# MCU089A_F280025C_Device.net
KiCad netlist of a schematic drawn in Altium Designer
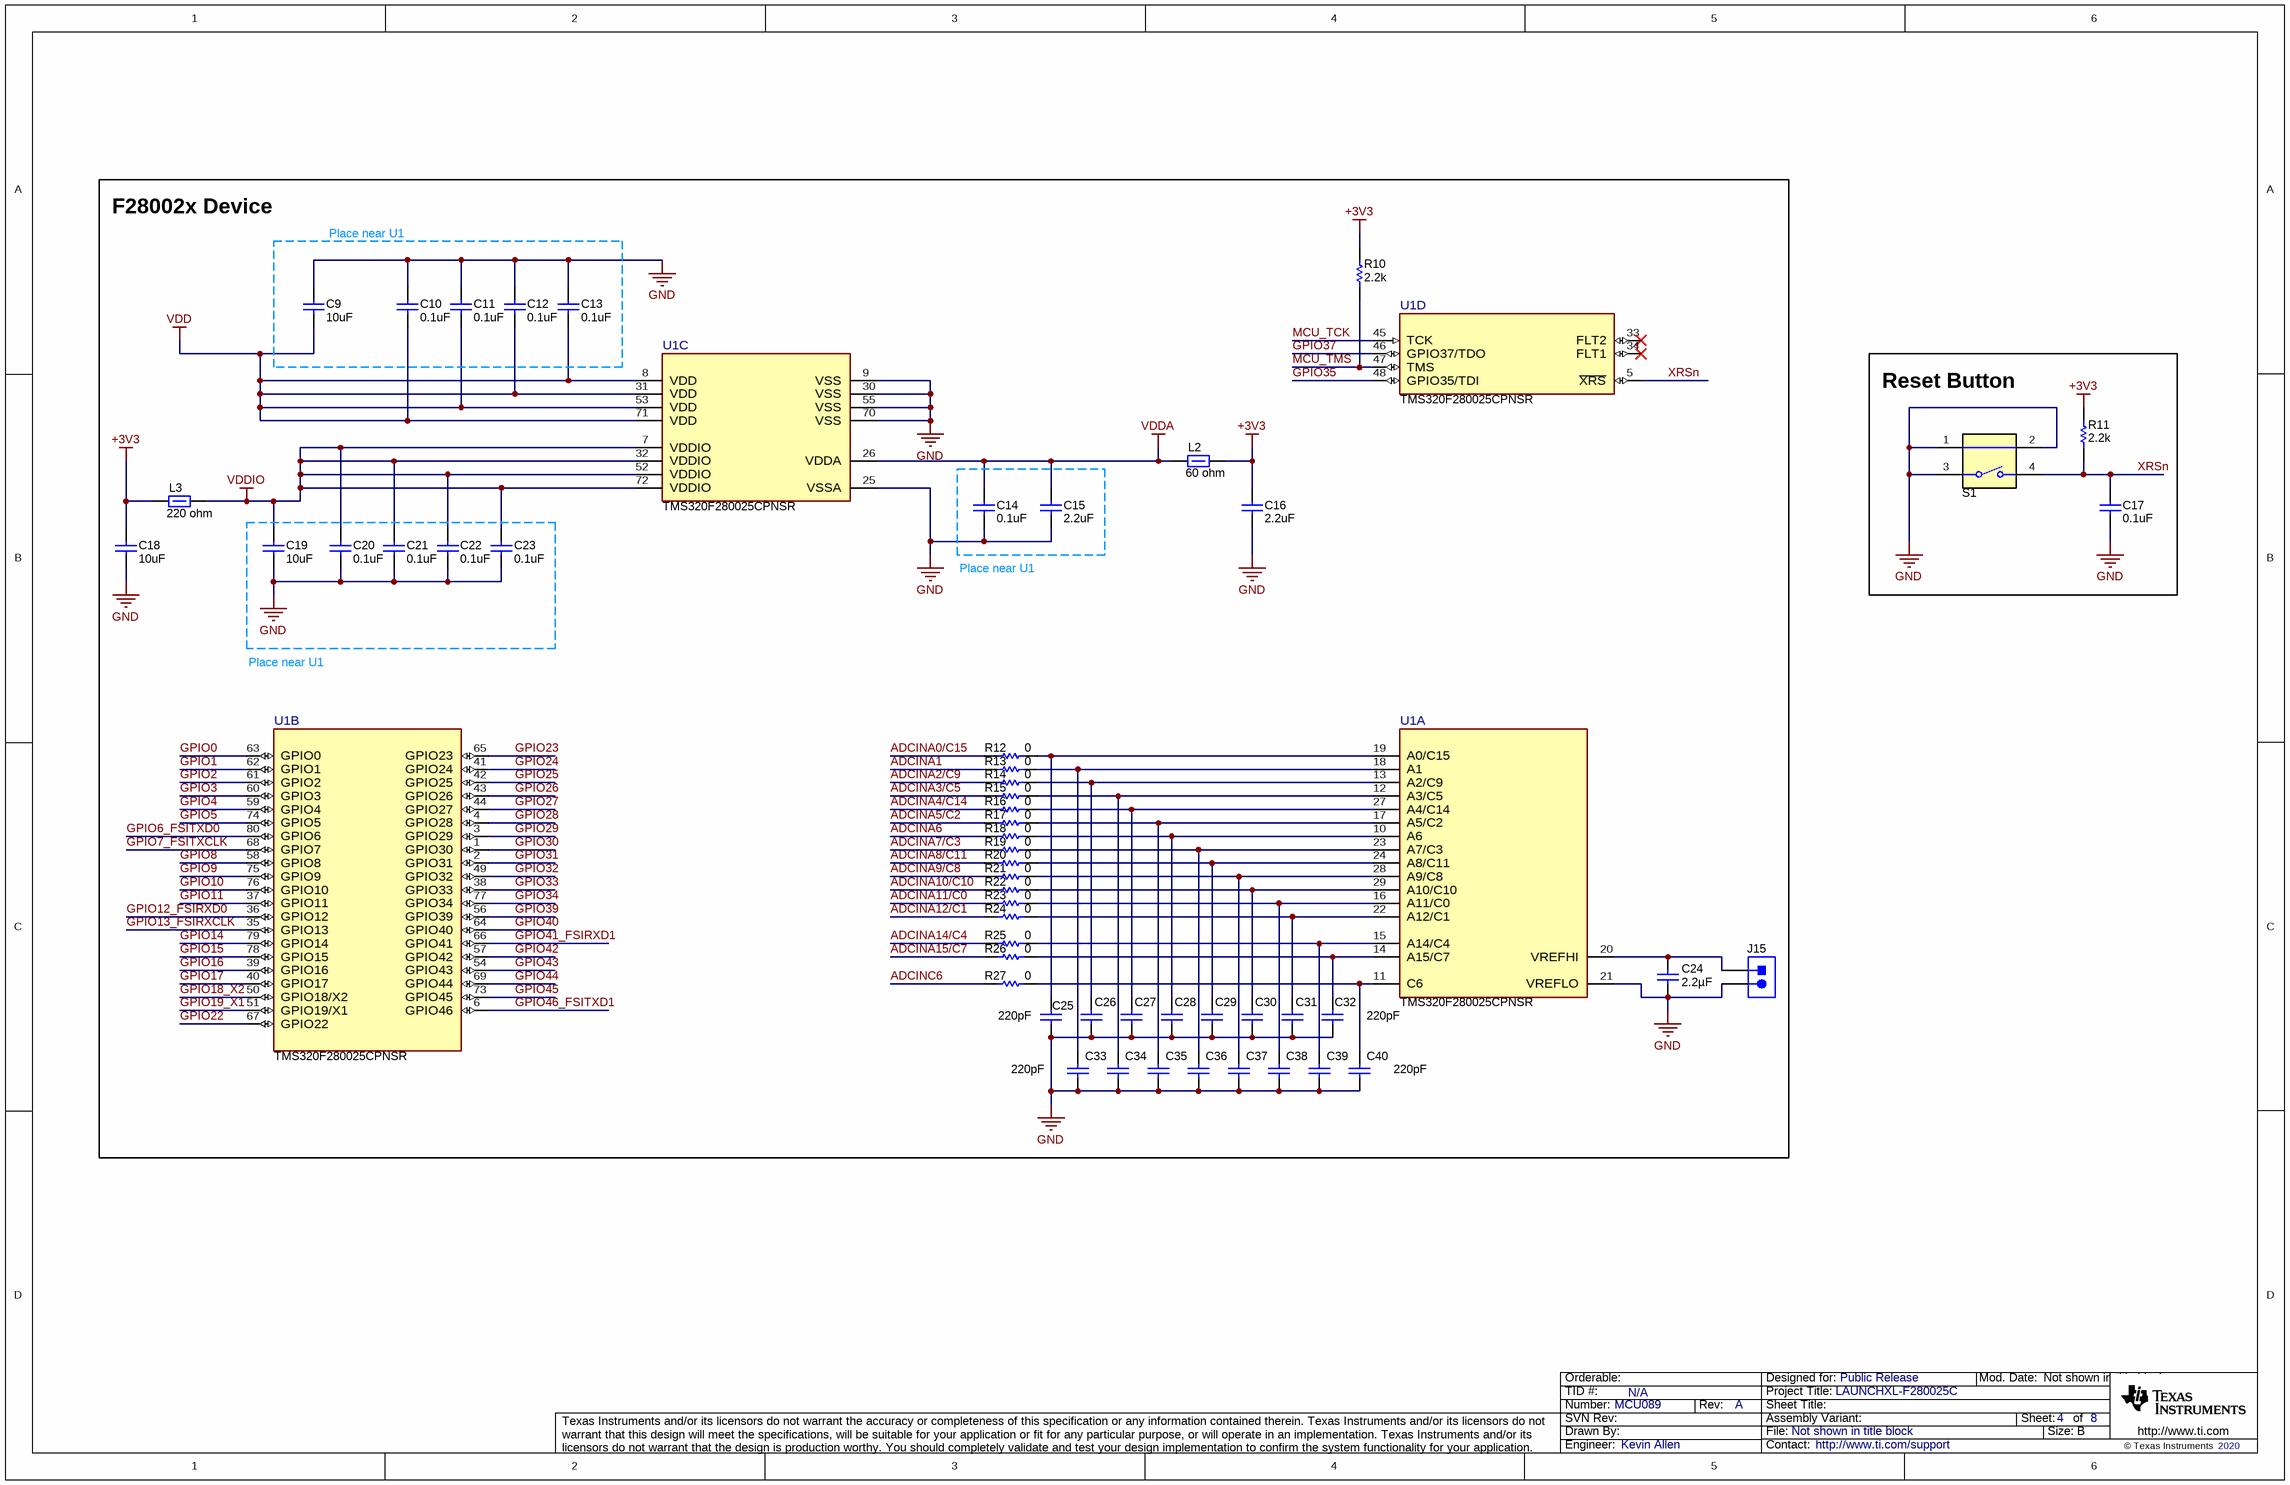
[diagram p0: MCU089A_F280025C_Device.SchDoc]

(export (version "E")
  (design (tool "Eeschema 10.0.6"))
  (components
    (comp (ref "C9")
      (value "GRM188R61A106ME69D")
      (footprint "0603")
      (description "CAP, CERM, 10 uF, 10 V, +/- 20%, X5R, 0603")
      (fields
        (field (name "VALUEDISPLAYED") "10uF")
        (field (name "MANUFACTURER") "MuRata")
        (field (name "PUBLISHER") "Texas Instruments")
      )
      (libsource (lib "Altium Vault - TI") (part "Capacitor"))
    )
    (comp (ref "C10")
      (value "GRM155R71A104KA01D")
      (footprint "0402")
      (description "CAP, CERM, 0.1 uF, 10 V, +/- 10%, X7R, 0402")
      (fields
        (field (name "VALUEDISPLAYED") "0.1uF")
        (field (name "MANUFACTURER") "MuRata")
        (field (name "PUBLISHER") "Texas Instruments")
      )
      (libsource (lib "Altium Vault - TI") (part "Capacitor"))
    )
    (comp (ref "C11")
      (value "GRM155R71A104KA01D")
      (footprint "0402")
      (description "CAP, CERM, 0.1 uF, 10 V, +/- 10%, X7R, 0402")
      (fields
        (field (name "VALUEDISPLAYED") "0.1uF")
        (field (name "MANUFACTURER") "MuRata")
        (field (name "PUBLISHER") "Texas Instruments")
      )
      (libsource (lib "Altium Vault - TI") (part "Capacitor"))
    )
    (comp (ref "C12")
      (value "GRM155R71A104KA01D")
      (footprint "0402")
      (description "CAP, CERM, 0.1 uF, 10 V, +/- 10%, X7R, 0402")
      (fields
        (field (name "VALUEDISPLAYED") "0.1uF")
        (field (name "MANUFACTURER") "MuRata")
        (field (name "PUBLISHER") "Texas Instruments")
      )
      (libsource (lib "Altium Vault - TI") (part "Capacitor"))
    )
    (comp (ref "C13")
      (value "GRM155R71A104KA01D")
      (footprint "0402")
      (description "CAP, CERM, 0.1 uF, 10 V, +/- 10%, X7R, 0402")
      (fields
        (field (name "VALUEDISPLAYED") "0.1uF")
        (field (name "MANUFACTURER") "MuRata")
        (field (name "PUBLISHER") "Texas Instruments")
      )
      (libsource (lib "Altium Vault - TI") (part "Capacitor"))
    )
    (comp (ref "C14")
      (value "GRM155R71A104KA01D")
      (footprint "0402")
      (description "CAP, CERM, 0.1 uF, 10 V, +/- 10%, X7R, 0402")
      (fields
        (field (name "VALUEDISPLAYED") "0.1uF")
        (field (name "MANUFACTURER") "MuRata")
        (field (name "PUBLISHER") "Texas Instruments")
      )
      (libsource (lib "Altium Vault - TI") (part "Capacitor"))
    )
    (comp (ref "C15")
      (value "GRM188R61A225KE34D")
      (footprint "0603")
      (description "CAP, CERM, 2.2 uF, 10 V, +/- 10%, X5R, 0603")
      (fields
        (field (name "VALUEDISPLAYED") "2.2uF")
        (field (name "MANUFACTURER") "MuRata")
        (field (name "PUBLISHER") "Texas Instruments")
      )
      (libsource (lib "Altium Vault - TI") (part "Capacitor"))
    )
    (comp (ref "C16")
      (value "GRM188R61A225KE34D")
      (footprint "0603")
      (description "CAP, CERM, 2.2 uF, 10 V, +/- 10%, X5R, 0603")
      (fields
        (field (name "VALUEDISPLAYED") "2.2uF")
        (field (name "MANUFACTURER") "MuRata")
        (field (name "PUBLISHER") "Texas Instruments")
      )
      (libsource (lib "Altium Vault - TI") (part "Capacitor"))
    )
    (comp (ref "C17")
      (value "GRM155R71A104KA01D")
      (footprint "0402")
      (description "CAP, CERM, 0.1 uF, 10 V, +/- 10%, X7R, 0402")
      (fields
        (field (name "VALUEDISPLAYED") "0.1uF")
        (field (name "MANUFACTURER") "MuRata")
        (field (name "PUBLISHER") "Texas Instruments")
      )
      (libsource (lib "Altium Vault - TI") (part "Capacitor"))
    )
    (comp (ref "C18")
      (value "GRM188R61A106ME69D")
      (footprint "0603")
      (description "CAP, CERM, 10 uF, 10 V, +/- 20%, X5R, 0603")
      (fields
        (field (name "VALUEDISPLAYED") "10uF")
        (field (name "MANUFACTURER") "MuRata")
        (field (name "PUBLISHER") "Texas Instruments")
      )
      (libsource (lib "Altium Vault - TI") (part "Capacitor"))
    )
    (comp (ref "C19")
      (value "GRM188R61A106ME69D")
      (footprint "0603")
      (description "CAP, CERM, 10 uF, 10 V, +/- 20%, X5R, 0603")
      (fields
        (field (name "VALUEDISPLAYED") "10uF")
        (field (name "MANUFACTURER") "MuRata")
        (field (name "PUBLISHER") "Texas Instruments")
      )
      (libsource (lib "Altium Vault - TI") (part "Capacitor"))
    )
    (comp (ref "C20")
      (value "GRM155R71A104KA01D")
      (footprint "0402")
      (description "CAP, CERM, 0.1 uF, 10 V, +/- 10%, X7R, 0402")
      (fields
        (field (name "VALUEDISPLAYED") "0.1uF")
        (field (name "MANUFACTURER") "MuRata")
        (field (name "PUBLISHER") "Texas Instruments")
      )
      (libsource (lib "Altium Vault - TI") (part "Capacitor"))
    )
    (comp (ref "C21")
      (value "GRM155R71A104KA01D")
      (footprint "0402")
      (description "CAP, CERM, 0.1 uF, 10 V, +/- 10%, X7R, 0402")
      (fields
        (field (name "VALUEDISPLAYED") "0.1uF")
        (field (name "MANUFACTURER") "MuRata")
        (field (name "PUBLISHER") "Texas Instruments")
      )
      (libsource (lib "Altium Vault - TI") (part "Capacitor"))
    )
    (comp (ref "C22")
      (value "GRM155R71A104KA01D")
      (footprint "0402")
      (description "CAP, CERM, 0.1 uF, 10 V, +/- 10%, X7R, 0402")
      (fields
        (field (name "VALUEDISPLAYED") "0.1uF")
        (field (name "MANUFACTURER") "MuRata")
        (field (name "PUBLISHER") "Texas Instruments")
      )
      (libsource (lib "Altium Vault - TI") (part "Capacitor"))
    )
    (comp (ref "C23")
      (value "GRM155R71A104KA01D")
      (footprint "0402")
      (description "CAP, CERM, 0.1 uF, 10 V, +/- 10%, X7R, 0402")
      (fields
        (field (name "VALUEDISPLAYED") "0.1uF")
        (field (name "MANUFACTURER") "MuRata")
        (field (name "PUBLISHER") "Texas Instruments")
      )
      (libsource (lib "Altium Vault - TI") (part "Capacitor"))
    )
    (comp (ref "C24")
      (value "GRM188R61A225KE34D")
      (footprint "0603")
      (description "CAP, CERM, 2.2 uF, 10 V, +/- 10%, X5R, 0603")
      (fields
        (field (name "MANUFACTURER") "MuRata")
        (field (name "CAP_F") "2.2µF")
        (field (name "PUBLISHER") "Texas Instruments")
      )
      (libsource (lib "Altium Vault - TI") (part "Capacitor"))
    )
    (comp (ref "C25")
      (value "C1005C0G1H221F050BA")
      (footprint "0402")
      (description "CAP, CERM, 220 pF, 50 V, +/- 1%, C0G/NP0, 0402")
      (fields
        (field (name "MANUFACTURER") "TDK")
        (field (name "CAP_F") "220pF")
        (field (name "PUBLISHER") "Texas Instruments")
      )
      (libsource (lib "Altium Vault - TI") (part "Capacitor"))
    )
    (comp (ref "C26")
      (value "C1005C0G1H221F050BA")
      (footprint "0402")
      (description "CAP, CERM, 220 pF, 50 V, +/- 1%, C0G/NP0, 0402")
      (fields (field (name "MANUFACTURER") "TDK") (field (name "PUBLISHER") "Texas Instruments"))
      (libsource (lib "Altium Vault - TI") (part "Capacitor"))
    )
    (comp (ref "C27")
      (value "C1005C0G1H221F050BA")
      (footprint "0402")
      (description "CAP, CERM, 220 pF, 50 V, +/- 1%, C0G/NP0, 0402")
      (fields (field (name "MANUFACTURER") "TDK") (field (name "PUBLISHER") "Texas Instruments"))
      (libsource (lib "Altium Vault - TI") (part "Capacitor"))
    )
    (comp (ref "C28")
      (value "C1005C0G1H221F050BA")
      (footprint "0402")
      (description "CAP, CERM, 220 pF, 50 V, +/- 1%, C0G/NP0, 0402")
      (fields (field (name "MANUFACTURER") "TDK") (field (name "PUBLISHER") "Texas Instruments"))
      (libsource (lib "Altium Vault - TI") (part "Capacitor"))
    )
    (comp (ref "C29")
      (value "C1005C0G1H221F050BA")
      (footprint "0402")
      (description "CAP, CERM, 220 pF, 50 V, +/- 1%, C0G/NP0, 0402")
      (fields (field (name "MANUFACTURER") "TDK") (field (name "PUBLISHER") "Texas Instruments"))
      (libsource (lib "Altium Vault - TI") (part "Capacitor"))
    )
    (comp (ref "C30")
      (value "C1005C0G1H221F050BA")
      (footprint "0402")
      (description "CAP, CERM, 220 pF, 50 V, +/- 1%, C0G/NP0, 0402")
      (fields (field (name "MANUFACTURER") "TDK") (field (name "PUBLISHER") "Texas Instruments"))
      (libsource (lib "Altium Vault - TI") (part "Capacitor"))
    )
    (comp (ref "C31")
      (value "C1005C0G1H221F050BA")
      (footprint "0402")
      (description "CAP, CERM, 220 pF, 50 V, +/- 1%, C0G/NP0, 0402")
      (fields (field (name "MANUFACTURER") "TDK") (field (name "PUBLISHER") "Texas Instruments"))
      (libsource (lib "Altium Vault - TI") (part "Capacitor"))
    )
    (comp (ref "C32")
      (value "C1005C0G1H221F050BA")
      (footprint "0402")
      (description "CAP, CERM, 220 pF, 50 V, +/- 1%, C0G/NP0, 0402")
      (fields
        (field (name "MANUFACTURER") "TDK")
        (field (name "CAP_F") "220pF")
        (field (name "PUBLISHER") "Texas Instruments")
      )
      (libsource (lib "Altium Vault - TI") (part "Capacitor"))
    )
    (comp (ref "C33")
      (value "C1005C0G1H221F050BA")
      (footprint "0402")
      (description "CAP, CERM, 220 pF, 50 V, +/- 1%, C0G/NP0, 0402")
      (fields
        (field (name "MANUFACTURER") "TDK")
        (field (name "CAP_F") "220pF")
        (field (name "PUBLISHER") "Texas Instruments")
      )
      (libsource (lib "Altium Vault - TI") (part "Capacitor"))
    )
    (comp (ref "C34")
      (value "C1005C0G1H221F050BA")
      (footprint "0402")
      (description "CAP, CERM, 220 pF, 50 V, +/- 1%, C0G/NP0, 0402")
      (fields (field (name "MANUFACTURER") "TDK") (field (name "PUBLISHER") "Texas Instruments"))
      (libsource (lib "Altium Vault - TI") (part "Capacitor"))
    )
    (comp (ref "C35")
      (value "C1005C0G1H221F050BA")
      (footprint "0402")
      (description "CAP, CERM, 220 pF, 50 V, +/- 1%, C0G/NP0, 0402")
      (fields (field (name "MANUFACTURER") "TDK") (field (name "PUBLISHER") "Texas Instruments"))
      (libsource (lib "Altium Vault - TI") (part "Capacitor"))
    )
    (comp (ref "C36")
      (value "C1005C0G1H221F050BA")
      (footprint "0402")
      (description "CAP, CERM, 220 pF, 50 V, +/- 1%, C0G/NP0, 0402")
      (fields (field (name "MANUFACTURER") "TDK") (field (name "PUBLISHER") "Texas Instruments"))
      (libsource (lib "Altium Vault - TI") (part "Capacitor"))
    )
    (comp (ref "C37")
      (value "C1005C0G1H221F050BA")
      (footprint "0402")
      (description "CAP, CERM, 220 pF, 50 V, +/- 1%, C0G/NP0, 0402")
      (fields (field (name "MANUFACTURER") "TDK") (field (name "PUBLISHER") "Texas Instruments"))
      (libsource (lib "Altium Vault - TI") (part "Capacitor"))
    )
    (comp (ref "C38")
      (value "C1005C0G1H221F050BA")
      (footprint "0402")
      (description "CAP, CERM, 220 pF, 50 V, +/- 1%, C0G/NP0, 0402")
      (fields (field (name "MANUFACTURER") "TDK") (field (name "PUBLISHER") "Texas Instruments"))
      (libsource (lib "Altium Vault - TI") (part "Capacitor"))
    )
    (comp (ref "C39")
      (value "C1005C0G1H221F050BA")
      (footprint "0402")
      (description "CAP, CERM, 220 pF, 50 V, +/- 1%, C0G/NP0, 0402")
      (fields (field (name "MANUFACTURER") "TDK") (field (name "PUBLISHER") "Texas Instruments"))
      (libsource (lib "Altium Vault - TI") (part "Capacitor"))
    )
    (comp (ref "C40")
      (value "C1005C0G1H221F050BA")
      (footprint "0402")
      (description "CAP, CERM, 220 pF, 50 V, +/- 1%, C0G/NP0, 0402")
      (fields
        (field (name "MANUFACTURER") "TDK")
        (field (name "CAP_F") "220pF")
        (field (name "PUBLISHER") "Texas Instruments")
      )
      (libsource (lib "Altium Vault - TI") (part "Capacitor"))
    )
    (comp (ref "J15")
      (value "61300211121")
      (footprint "WURTH_61300211121")
      (description "Header, 2.54 mm, 2x1, Gold, TH")
      (fields (field (name "MANUFACTURER") "Wurth Elektronik") (field (name "PUBLISHER") "Texas Instruments"))
      (libsource (lib "Altium Vault - TI") (part "CMP-0054794-1"))
    )
    (comp (ref "L2")
      (value "60 ohm")
      (footprint "0805_HV")
      (description "Ferrite Bead, 60 ohm @ 100 MHz, 3 A, 0805")
      (fields
        (field (name "MANUFACTURER") "Wurth Elektronik")
        (field (name "PARTNUMBER") "742792063")
        (field (name "PUBLISHER") "Texas Instruments")
      )
      (libsource (lib "Altium Vault - TI") (part "Ferrite_Bead"))
    )
    (comp (ref "L3")
      (value "742792022")
      (footprint "0805_HV")
      (description "Ferrite Bead, 220 ohm @ 100 MHz, 2 A, 0805")
      (fields
        (field (name "MANUFACTURER") "Wurth Elektronik")
        (field (name "VALUEDISPLAYED") "220 ohm")
        (field (name "PUBLISHER") "Texas Instruments")
      )
      (libsource (lib "Altium Vault - TI") (part "Ferrite_Bead"))
    )
    (comp (ref "R10")
      (value "CRCW04022K20JNED")
      (footprint "0402")
      (description "RES, 2.2 k, 5%, 0.063 W, AEC-Q200 Grade 0, 0402")
      (fields (field (name "VALUEDISPLAYED") "2.2k") (field (name "MANUFACTURER") "Vishay-Dale"))
      (libsource (lib "Altium Vault - TI") (part "Resistor"))
    )
    (comp (ref "R11")
      (value "CRCW04022K20JNED")
      (footprint "0402")
      (description "RES, 2.2 k, 5%, 0.063 W, AEC-Q200 Grade 0, 0402")
      (fields (field (name "VALUEDISPLAYED") "2.2k") (field (name "MANUFACTURER") "Vishay-Dale"))
      (libsource (lib "Altium Vault - TI") (part "Resistor"))
    )
    (comp (ref "R12")
      (value "ERJ-2GE0R00X")
      (footprint "0402")
      (description "RES, 0, 5%, 0.1 W, AEC-Q200 Grade 0, 0402")
      (fields (field (name "MANUFACTURER") "Panasonic") (field (name "VALUEDISPLAYED") "0"))
      (libsource (lib "Altium Vault - TI") (part "Resistor"))
    )
    (comp (ref "R13")
      (value "ERJ-2GE0R00X")
      (footprint "0402")
      (description "RES, 0, 5%, 0.1 W, AEC-Q200 Grade 0, 0402")
      (fields (field (name "MANUFACTURER") "Panasonic") (field (name "VALUEDISPLAYED") "0"))
      (libsource (lib "Altium Vault - TI") (part "Resistor"))
    )
    (comp (ref "R14")
      (value "ERJ-2GE0R00X")
      (footprint "0402")
      (description "RES, 0, 5%, 0.1 W, AEC-Q200 Grade 0, 0402")
      (fields (field (name "MANUFACTURER") "Panasonic") (field (name "VALUEDISPLAYED") "0"))
      (libsource (lib "Altium Vault - TI") (part "Resistor"))
    )
    (comp (ref "R15")
      (value "ERJ-2GE0R00X")
      (footprint "0402")
      (description "RES, 0, 5%, 0.1 W, AEC-Q200 Grade 0, 0402")
      (fields (field (name "MANUFACTURER") "Panasonic") (field (name "VALUEDISPLAYED") "0"))
      (libsource (lib "Altium Vault - TI") (part "Resistor"))
    )
    (comp (ref "R16")
      (value "ERJ-2GE0R00X")
      (footprint "0402")
      (description "RES, 0, 5%, 0.1 W, AEC-Q200 Grade 0, 0402")
      (fields (field (name "MANUFACTURER") "Panasonic") (field (name "VALUEDISPLAYED") "0"))
      (libsource (lib "Altium Vault - TI") (part "Resistor"))
    )
    (comp (ref "R17")
      (value "ERJ-2GE0R00X")
      (footprint "0402")
      (description "RES, 0, 5%, 0.1 W, AEC-Q200 Grade 0, 0402")
      (fields (field (name "MANUFACTURER") "Panasonic") (field (name "VALUEDISPLAYED") "0"))
      (libsource (lib "Altium Vault - TI") (part "Resistor"))
    )
    (comp (ref "R18")
      (value "ERJ-2GE0R00X")
      (footprint "0402")
      (description "RES, 0, 5%, 0.1 W, AEC-Q200 Grade 0, 0402")
      (fields (field (name "MANUFACTURER") "Panasonic") (field (name "VALUEDISPLAYED") "0"))
      (libsource (lib "Altium Vault - TI") (part "Resistor"))
    )
    (comp (ref "R19")
      (value "ERJ-2GE0R00X")
      (footprint "0402")
      (description "RES, 0, 5%, 0.1 W, AEC-Q200 Grade 0, 0402")
      (fields (field (name "MANUFACTURER") "Panasonic") (field (name "VALUEDISPLAYED") "0"))
      (libsource (lib "Altium Vault - TI") (part "Resistor"))
    )
    (comp (ref "R20")
      (value "ERJ-2GE0R00X")
      (footprint "0402")
      (description "RES, 0, 5%, 0.1 W, AEC-Q200 Grade 0, 0402")
      (fields (field (name "MANUFACTURER") "Panasonic") (field (name "VALUEDISPLAYED") "0"))
      (libsource (lib "Altium Vault - TI") (part "Resistor"))
    )
    (comp (ref "R21")
      (value "ERJ-2GE0R00X")
      (footprint "0402")
      (description "RES, 0, 5%, 0.1 W, AEC-Q200 Grade 0, 0402")
      (fields (field (name "MANUFACTURER") "Panasonic") (field (name "VALUEDISPLAYED") "0"))
      (libsource (lib "Altium Vault - TI") (part "Resistor"))
    )
    (comp (ref "R22")
      (value "ERJ-2GE0R00X")
      (footprint "0402")
      (description "RES, 0, 5%, 0.1 W, AEC-Q200 Grade 0, 0402")
      (fields (field (name "MANUFACTURER") "Panasonic") (field (name "VALUEDISPLAYED") "0"))
      (libsource (lib "Altium Vault - TI") (part "Resistor"))
    )
    (comp (ref "R23")
      (value "ERJ-2GE0R00X")
      (footprint "0402")
      (description "RES, 0, 5%, 0.1 W, AEC-Q200 Grade 0, 0402")
      (fields (field (name "MANUFACTURER") "Panasonic") (field (name "VALUEDISPLAYED") "0"))
      (libsource (lib "Altium Vault - TI") (part "Resistor"))
    )
    (comp (ref "R24")
      (value "ERJ-2GE0R00X")
      (footprint "0402")
      (description "RES, 0, 5%, 0.1 W, AEC-Q200 Grade 0, 0402")
      (fields (field (name "MANUFACTURER") "Panasonic") (field (name "VALUEDISPLAYED") "0"))
      (libsource (lib "Altium Vault - TI") (part "Resistor"))
    )
    (comp (ref "R25")
      (value "ERJ-2GE0R00X")
      (footprint "0402")
      (description "RES, 0, 5%, 0.1 W, AEC-Q200 Grade 0, 0402")
      (fields (field (name "MANUFACTURER") "Panasonic") (field (name "VALUEDISPLAYED") "0"))
      (libsource (lib "Altium Vault - TI") (part "Resistor"))
    )
    (comp (ref "R26")
      (value "ERJ-2GE0R00X")
      (footprint "0402")
      (description "RES, 0, 5%, 0.1 W, AEC-Q200 Grade 0, 0402")
      (fields (field (name "MANUFACTURER") "Panasonic") (field (name "VALUEDISPLAYED") "0"))
      (libsource (lib "Altium Vault - TI") (part "Resistor"))
    )
    (comp (ref "R27")
      (value "ERJ-2GE0R00X")
      (footprint "0402")
      (description "RES, 0, 5%, 0.1 W, AEC-Q200 Grade 0, 0402")
      (fields (field (name "MANUFACTURER") "Panasonic") (field (name "VALUEDISPLAYED") "0"))
      (libsource (lib "Altium Vault - TI") (part "Resistor"))
    )
    (comp (ref "S1")
      (value "1188E-1K2-V-TR")
      (footprint "SW_1188E")
      (description "Switch, SPST, 0.05 A, 12 VDC, SMD")
      (fields (field (name "MANUFACTURER") "Diptronics") (field (name "PUBLISHER") "Texas Instruments"))
      (libsource (lib "Altium Vault - TI") (part "SW_1188E"))
    )
    (comp (ref "U1")
      (value "TMS320F280025CPNSR")
      (footprint "PN0080A-MFG")
      (description "32-bit MCU with 100 MHz, FPU, TMU, 128-KB flash, CLB 80-LQFP -40 to 125")
      (fields
        (field (name "MANUFACTURER") "Texas Instruments")
        (field (name "PARTNUMBER") "TMS320F280025CPNSR")
      )
      (libsource (lib "Altium Vault - TI") (part "SYM-TMS320F280025CPNSR"))
    )
  )
  (nets
    (net (code "1") (name "+3V3") (class "Default")
      (node (ref "C16") (pin "1") (pinfunction "1_1") (pintype "passive"))
      (node (ref "C18") (pin "1") (pinfunction "1_1") (pintype "passive"))
      (node (ref "L2") (pin "2") (pinfunction "2_2") (pintype "passive"))
      (node (ref "L3") (pin "1") (pinfunction "1_1") (pintype "passive"))
      (node (ref "R10") (pin "2") (pinfunction "2_2") (pintype "passive"))
      (node (ref "R11") (pin "2") (pinfunction "2_2") (pintype "passive"))
    )
    (net (code "2") (name "/ADCINA0{slash}C15") (class "Default")
      (node (ref "R12") (pin "1") (pinfunction "1_1") (pintype "passive"))
    )
    (net (code "3") (name "/ADCINA1") (class "Default")
      (node (ref "R13") (pin "1") (pinfunction "1_1") (pintype "passive"))
    )
    (net (code "4") (name "/ADCINA2{slash}C9") (class "Default")
      (node (ref "R14") (pin "1") (pinfunction "1_1") (pintype "passive"))
    )
    (net (code "5") (name "/ADCINA3{slash}C5") (class "Default")
      (node (ref "R15") (pin "1") (pinfunction "1_1") (pintype "passive"))
    )
    (net (code "6") (name "/ADCINA4{slash}C14") (class "Default")
      (node (ref "R16") (pin "1") (pinfunction "1_1") (pintype "passive"))
    )
    (net (code "7") (name "/ADCINA5{slash}C2") (class "Default")
      (node (ref "R17") (pin "1") (pinfunction "1_1") (pintype "passive"))
    )
    (net (code "8") (name "/ADCINA6") (class "Default")
      (node (ref "R18") (pin "1") (pinfunction "1_1") (pintype "passive"))
    )
    (net (code "9") (name "/ADCINA7{slash}C3") (class "Default")
      (node (ref "R19") (pin "1") (pinfunction "1_1") (pintype "passive"))
    )
    (net (code "10") (name "/ADCINA8{slash}C11") (class "Default")
      (node (ref "R20") (pin "1") (pinfunction "1_1") (pintype "passive"))
    )
    (net (code "11") (name "/ADCINA9{slash}C8") (class "Default")
      (node (ref "R21") (pin "1") (pinfunction "1_1") (pintype "passive"))
    )
    (net (code "12") (name "/ADCINA10{slash}C10") (class "Default")
      (node (ref "R22") (pin "1") (pinfunction "1_1") (pintype "passive"))
    )
    (net (code "13") (name "/ADCINA11{slash}C0") (class "Default")
      (node (ref "R23") (pin "1") (pinfunction "1_1") (pintype "passive"))
    )
    (net (code "14") (name "/ADCINA12{slash}C1") (class "Default")
      (node (ref "R24") (pin "1") (pinfunction "1_1") (pintype "passive"))
    )
    (net (code "15") (name "/ADCINA14{slash}C4") (class "Default")
      (node (ref "R25") (pin "1") (pinfunction "1_1") (pintype "passive"))
    )
    (net (code "16") (name "/ADCINA15{slash}C7") (class "Default")
      (node (ref "R26") (pin "1") (pinfunction "1_1") (pintype "passive"))
    )
    (net (code "17") (name "/ADCINC6") (class "Default")
      (node (ref "R27") (pin "1") (pinfunction "1_1") (pintype "passive"))
    )
    (net (code "18") (name "/GPIO0") (class "Default")
      (node (ref "U1") (pin "63") (pinfunction "GPIO0_63") (pintype "bidirectional"))
    )
    (net (code "19") (name "/GPIO1") (class "Default")
      (node (ref "U1") (pin "62") (pinfunction "GPIO1_62") (pintype "bidirectional"))
    )
    (net (code "20") (name "/GPIO2") (class "Default")
      (node (ref "U1") (pin "61") (pinfunction "GPIO2_61") (pintype "bidirectional"))
    )
    (net (code "21") (name "/GPIO3") (class "Default")
      (node (ref "U1") (pin "60") (pinfunction "GPIO3_60") (pintype "bidirectional"))
    )
    (net (code "22") (name "/GPIO4") (class "Default")
      (node (ref "U1") (pin "59") (pinfunction "GPIO4_59") (pintype "bidirectional"))
    )
    (net (code "23") (name "/GPIO5") (class "Default")
      (node (ref "U1") (pin "74") (pinfunction "GPIO5_74") (pintype "bidirectional"))
    )
    (net (code "24") (name "/GPIO6_FSITXD0") (class "Default")
      (node (ref "U1") (pin "80") (pinfunction "GPIO6_80") (pintype "bidirectional"))
    )
    (net (code "25") (name "/GPIO7_FSITXCLK") (class "Default")
      (node (ref "U1") (pin "68") (pinfunction "GPIO7_68") (pintype "bidirectional"))
    )
    (net (code "26") (name "/GPIO8") (class "Default")
      (node (ref "U1") (pin "58") (pinfunction "GPIO8_58") (pintype "bidirectional"))
    )
    (net (code "27") (name "/GPIO9") (class "Default")
      (node (ref "U1") (pin "75") (pinfunction "GPIO9_75") (pintype "bidirectional"))
    )
    (net (code "28") (name "/GPIO10") (class "Default")
      (node (ref "U1") (pin "76") (pinfunction "GPIO10_76") (pintype "bidirectional"))
    )
    (net (code "29") (name "/GPIO11") (class "Default")
      (node (ref "U1") (pin "37") (pinfunction "GPIO11_37") (pintype "bidirectional"))
    )
    (net (code "30") (name "/GPIO12_FSIRXD0") (class "Default")
      (node (ref "U1") (pin "36") (pinfunction "GPIO12_36") (pintype "bidirectional"))
    )
    (net (code "31") (name "/GPIO13_FSIRXCLK") (class "Default")
      (node (ref "U1") (pin "35") (pinfunction "GPIO13_35") (pintype "bidirectional"))
    )
    (net (code "32") (name "/GPIO14") (class "Default")
      (node (ref "U1") (pin "79") (pinfunction "GPIO14_79") (pintype "bidirectional"))
    )
    (net (code "33") (name "/GPIO15") (class "Default")
      (node (ref "U1") (pin "78") (pinfunction "GPIO15_78") (pintype "bidirectional"))
    )
    (net (code "34") (name "/GPIO16") (class "Default")
      (node (ref "U1") (pin "39") (pinfunction "GPIO16_39") (pintype "bidirectional"))
    )
    (net (code "35") (name "/GPIO17") (class "Default")
      (node (ref "U1") (pin "40") (pinfunction "GPIO17_40") (pintype "bidirectional"))
    )
    (net (code "36") (name "/GPIO18_X2") (class "Default")
      (node (ref "U1") (pin "50") (pinfunction "GPIO18/X2_50") (pintype "bidirectional"))
    )
    (net (code "37") (name "/GPIO19_X1") (class "Default")
      (node (ref "U1") (pin "51") (pinfunction "GPIO19/X1_51") (pintype "bidirectional"))
    )
    (net (code "38") (name "/GPIO22") (class "Default")
      (node (ref "U1") (pin "67") (pinfunction "GPIO22_67") (pintype "bidirectional"))
    )
    (net (code "39") (name "/GPIO23") (class "Default")
      (node (ref "U1") (pin "65") (pinfunction "GPIO23_65") (pintype "bidirectional"))
    )
    (net (code "40") (name "/GPIO24") (class "Default")
      (node (ref "U1") (pin "41") (pinfunction "GPIO24_41") (pintype "bidirectional"))
    )
    (net (code "41") (name "/GPIO25") (class "Default")
      (node (ref "U1") (pin "42") (pinfunction "GPIO25_42") (pintype "bidirectional"))
    )
    (net (code "42") (name "/GPIO26") (class "Default")
      (node (ref "U1") (pin "43") (pinfunction "GPIO26_43") (pintype "bidirectional"))
    )
    (net (code "43") (name "/GPIO27") (class "Default")
      (node (ref "U1") (pin "44") (pinfunction "GPIO27_44") (pintype "bidirectional"))
    )
    (net (code "44") (name "/GPIO28") (class "Default")
      (node (ref "U1") (pin "4") (pinfunction "GPIO28_4") (pintype "bidirectional"))
    )
    (net (code "45") (name "/GPIO29") (class "Default")
      (node (ref "U1") (pin "3") (pinfunction "GPIO29_3") (pintype "bidirectional"))
    )
    (net (code "46") (name "/GPIO30") (class "Default")
      (node (ref "U1") (pin "1") (pinfunction "GPIO30_1") (pintype "bidirectional"))
    )
    (net (code "47") (name "/GPIO31") (class "Default")
      (node (ref "U1") (pin "2") (pinfunction "GPIO31_2") (pintype "bidirectional"))
    )
    (net (code "48") (name "/GPIO32") (class "Default")
      (node (ref "U1") (pin "49") (pinfunction "GPIO32_49") (pintype "bidirectional"))
    )
    (net (code "49") (name "/GPIO33") (class "Default")
      (node (ref "U1") (pin "38") (pinfunction "GPIO33_38") (pintype "bidirectional"))
    )
    (net (code "50") (name "/GPIO34") (class "Default")
      (node (ref "U1") (pin "77") (pinfunction "GPIO34_77") (pintype "bidirectional"))
    )
    (net (code "51") (name "/GPIO35") (class "Default")
      (node (ref "U1") (pin "48") (pinfunction "GPIO35/TDI_48") (pintype "bidirectional"))
    )
    (net (code "52") (name "/GPIO37") (class "Default")
      (node (ref "U1") (pin "46") (pinfunction "GPIO37/TDO_46") (pintype "bidirectional"))
    )
    (net (code "53") (name "/GPIO39") (class "Default")
      (node (ref "U1") (pin "56") (pinfunction "GPIO39_56") (pintype "bidirectional"))
    )
    (net (code "54") (name "/GPIO40") (class "Default")
      (node (ref "U1") (pin "64") (pinfunction "GPIO40_64") (pintype "bidirectional"))
    )
    (net (code "55") (name "/GPIO41_FSIRXD1") (class "Default")
      (node (ref "U1") (pin "66") (pinfunction "GPIO41_66") (pintype "bidirectional"))
    )
    (net (code "56") (name "/GPIO42") (class "Default")
      (node (ref "U1") (pin "57") (pinfunction "GPIO42_57") (pintype "bidirectional"))
    )
    (net (code "57") (name "/GPIO43") (class "Default")
      (node (ref "U1") (pin "54") (pinfunction "GPIO43_54") (pintype "bidirectional"))
    )
    (net (code "58") (name "/GPIO44") (class "Default")
      (node (ref "U1") (pin "69") (pinfunction "GPIO44_69") (pintype "bidirectional"))
    )
    (net (code "59") (name "/GPIO45") (class "Default")
      (node (ref "U1") (pin "73") (pinfunction "GPIO45_73") (pintype "bidirectional"))
    )
    (net (code "60") (name "/GPIO46_FSITXD1") (class "Default")
      (node (ref "U1") (pin "6") (pinfunction "GPIO46_6") (pintype "bidirectional"))
    )
    (net (code "61") (name "/MCU_TCK") (class "Default")
      (node (ref "U1") (pin "45") (pinfunction "TCK_45") (pintype "input"))
    )
    (net (code "62") (name "/MCU_TMS") (class "Default")
      (node (ref "R10") (pin "1") (pinfunction "1_1") (pintype "passive"))
      (node (ref "U1") (pin "47") (pinfunction "TMS_47") (pintype "bidirectional"))
    )
    (net (code "63") (name "/XRSn") (class "Default")
      (node (ref "C17") (pin "2") (pinfunction "2_2") (pintype "passive"))
      (node (ref "R11") (pin "1") (pinfunction "1_1") (pintype "passive"))
      (node (ref "S1") (pin "4") (pinfunction "4_4") (pintype "passive"))
      (node (ref "U1") (pin "5") (pinfunction "~{XRS}_5") (pintype "bidirectional"))
    )
    (net (code "64") (name "GND") (class "Default")
      (node (ref "C10") (pin "2") (pinfunction "2_2") (pintype "passive"))
      (node (ref "C11") (pin "2") (pinfunction "2_2") (pintype "passive"))
      (node (ref "C12") (pin "2") (pinfunction "2_2") (pintype "passive"))
      (node (ref "C13") (pin "2") (pinfunction "2_2") (pintype "passive"))
      (node (ref "C14") (pin "1") (pinfunction "1_1") (pintype "passive"))
      (node (ref "C15") (pin "2") (pinfunction "2_2") (pintype "passive"))
      (node (ref "C16") (pin "2") (pinfunction "2_2") (pintype "passive"))
      (node (ref "C17") (pin "1") (pinfunction "1_1") (pintype "passive"))
      (node (ref "C18") (pin "2") (pinfunction "2_2") (pintype "passive"))
      (node (ref "C19") (pin "2") (pinfunction "2_2") (pintype "passive"))
      (node (ref "C20") (pin "1") (pinfunction "1_1") (pintype "passive"))
      (node (ref "C21") (pin "1") (pinfunction "1_1") (pintype "passive"))
      (node (ref "C22") (pin "1") (pinfunction "1_1") (pintype "passive"))
      (node (ref "C23") (pin "1") (pinfunction "1_1") (pintype "passive"))
      (node (ref "C24") (pin "2") (pinfunction "2_2") (pintype "passive"))
      (node (ref "C25") (pin "2") (pinfunction "2_2") (pintype "passive"))
      (node (ref "C26") (pin "2") (pinfunction "2_2") (pintype "passive"))
      (node (ref "C27") (pin "2") (pinfunction "2_2") (pintype "passive"))
      (node (ref "C28") (pin "2") (pinfunction "2_2") (pintype "passive"))
      (node (ref "C29") (pin "2") (pinfunction "2_2") (pintype "passive"))
      (node (ref "C30") (pin "2") (pinfunction "2_2") (pintype "passive"))
      (node (ref "C31") (pin "2") (pinfunction "2_2") (pintype "passive"))
      (node (ref "C32") (pin "2") (pinfunction "2_2") (pintype "passive"))
      (node (ref "C33") (pin "2") (pinfunction "2_2") (pintype "passive"))
      (node (ref "C34") (pin "2") (pinfunction "2_2") (pintype "passive"))
      (node (ref "C35") (pin "2") (pinfunction "2_2") (pintype "passive"))
      (node (ref "C36") (pin "2") (pinfunction "2_2") (pintype "passive"))
      (node (ref "C37") (pin "2") (pinfunction "2_2") (pintype "passive"))
      (node (ref "C38") (pin "2") (pinfunction "2_2") (pintype "passive"))
      (node (ref "C39") (pin "2") (pinfunction "2_2") (pintype "passive"))
      (node (ref "C40") (pin "2") (pinfunction "2_2") (pintype "passive"))
      (node (ref "C9") (pin "1") (pinfunction "1_1") (pintype "passive"))
      (node (ref "J15") (pin "2") (pinfunction "2_2") (pintype "passive"))
      (node (ref "S1") (pin "1") (pinfunction "1_1") (pintype "passive"))
      (node (ref "S1") (pin "2") (pinfunction "2_2") (pintype "passive"))
      (node (ref "S1") (pin "3") (pinfunction "3_3") (pintype "passive"))
      (node (ref "U1") (pin "21") (pinfunction "VREFLO_21") (pintype "passive"))
      (node (ref "U1") (pin "25") (pinfunction "VSSA_25") (pintype "power_in"))
      (node (ref "U1") (pin "30") (pinfunction "VSS_30") (pintype "power_in"))
      (node (ref "U1") (pin "55") (pinfunction "VSS_55") (pintype "power_in"))
      (node (ref "U1") (pin "70") (pinfunction "VSS_70") (pintype "power_in"))
      (node (ref "U1") (pin "9") (pinfunction "VSS_9") (pintype "power_in"))
    )
    (net (code "65") (name "Net-(U1A-A0{slash}C15)") (class "Default")
      (node (ref "C25") (pin "1") (pinfunction "1_1") (pintype "passive"))
      (node (ref "R12") (pin "2") (pinfunction "2_2") (pintype "passive"))
      (node (ref "U1") (pin "19") (pinfunction "A0/C15_19") (pintype "passive"))
    )
    (net (code "66") (name "Net-(U1A-A1)") (class "Default")
      (node (ref "C33") (pin "1") (pinfunction "1_1") (pintype "passive"))
      (node (ref "R13") (pin "2") (pinfunction "2_2") (pintype "passive"))
      (node (ref "U1") (pin "18") (pinfunction "A1_18") (pintype "passive"))
    )
    (net (code "67") (name "Net-(U1A-A2{slash}C9)") (class "Default")
      (node (ref "C26") (pin "1") (pinfunction "1_1") (pintype "passive"))
      (node (ref "R14") (pin "2") (pinfunction "2_2") (pintype "passive"))
      (node (ref "U1") (pin "13") (pinfunction "A2/C9_13") (pintype "passive"))
    )
    (net (code "68") (name "Net-(U1A-A3{slash}C5)") (class "Default")
      (node (ref "C34") (pin "1") (pinfunction "1_1") (pintype "passive"))
      (node (ref "R15") (pin "2") (pinfunction "2_2") (pintype "passive"))
      (node (ref "U1") (pin "12") (pinfunction "A3/C5_12") (pintype "passive"))
    )
    (net (code "69") (name "Net-(U1A-A4{slash}C14)") (class "Default")
      (node (ref "C27") (pin "1") (pinfunction "1_1") (pintype "passive"))
      (node (ref "R16") (pin "2") (pinfunction "2_2") (pintype "passive"))
      (node (ref "U1") (pin "27") (pinfunction "A4/C14_27") (pintype "passive"))
    )
    (net (code "70") (name "Net-(U1A-A5{slash}C2)") (class "Default")
      (node (ref "C35") (pin "1") (pinfunction "1_1") (pintype "passive"))
      (node (ref "R17") (pin "2") (pinfunction "2_2") (pintype "passive"))
      (node (ref "U1") (pin "17") (pinfunction "A5/C2_17") (pintype "passive"))
    )
    (net (code "71") (name "Net-(U1A-A6)") (class "Default")
      (node (ref "C28") (pin "1") (pinfunction "1_1") (pintype "passive"))
      (node (ref "R18") (pin "2") (pinfunction "2_2") (pintype "passive"))
      (node (ref "U1") (pin "10") (pinfunction "A6_10") (pintype "passive"))
    )
    (net (code "72") (name "Net-(U1A-A7{slash}C3)") (class "Default")
      (node (ref "C36") (pin "1") (pinfunction "1_1") (pintype "passive"))
      (node (ref "R19") (pin "2") (pinfunction "2_2") (pintype "passive"))
      (node (ref "U1") (pin "23") (pinfunction "A7/C3_23") (pintype "passive"))
    )
    (net (code "73") (name "Net-(U1A-A8{slash}C11)") (class "Default")
      (node (ref "C29") (pin "1") (pinfunction "1_1") (pintype "passive"))
      (node (ref "R20") (pin "2") (pinfunction "2_2") (pintype "passive"))
      (node (ref "U1") (pin "24") (pinfunction "A8/C11_24") (pintype "passive"))
    )
    (net (code "74") (name "Net-(U1A-A9{slash}C8)") (class "Default")
      (node (ref "C37") (pin "1") (pinfunction "1_1") (pintype "passive"))
      (node (ref "R21") (pin "2") (pinfunction "2_2") (pintype "passive"))
      (node (ref "U1") (pin "28") (pinfunction "A9/C8_28") (pintype "passive"))
    )
    (net (code "75") (name "Net-(U1A-A10{slash}C10)") (class "Default")
      (node (ref "C30") (pin "1") (pinfunction "1_1") (pintype "passive"))
      (node (ref "R22") (pin "2") (pinfunction "2_2") (pintype "passive"))
      (node (ref "U1") (pin "29") (pinfunction "A10/C10_29") (pintype "passive"))
    )
    (net (code "76") (name "Net-(U1A-A11{slash}C0)") (class "Default")
      (node (ref "C38") (pin "1") (pinfunction "1_1") (pintype "passive"))
      (node (ref "R23") (pin "2") (pinfunction "2_2") (pintype "passive"))
      (node (ref "U1") (pin "16") (pinfunction "A11/C0_16") (pintype "passive"))
    )
    (net (code "77") (name "Net-(U1A-A12{slash}C1)") (class "Default")
      (node (ref "C31") (pin "1") (pinfunction "1_1") (pintype "passive"))
      (node (ref "R24") (pin "2") (pinfunction "2_2") (pintype "passive"))
      (node (ref "U1") (pin "22") (pinfunction "A12/C1_22") (pintype "passive"))
    )
    (net (code "78") (name "Net-(U1A-A14{slash}C4)") (class "Default")
      (node (ref "C39") (pin "1") (pinfunction "1_1") (pintype "passive"))
      (node (ref "R25") (pin "2") (pinfunction "2_2") (pintype "passive"))
      (node (ref "U1") (pin "15") (pinfunction "A14/C4_15") (pintype "passive"))
    )
    (net (code "79") (name "Net-(U1A-A15{slash}C7)") (class "Default")
      (node (ref "C32") (pin "1") (pinfunction "1_1") (pintype "passive"))
      (node (ref "R26") (pin "2") (pinfunction "2_2") (pintype "passive"))
      (node (ref "U1") (pin "14") (pinfunction "A15/C7_14") (pintype "passive"))
    )
    (net (code "80") (name "Net-(U1A-C6)") (class "Default")
      (node (ref "C40") (pin "1") (pinfunction "1_1") (pintype "passive"))
      (node (ref "R27") (pin "2") (pinfunction "2_2") (pintype "passive"))
      (node (ref "U1") (pin "11") (pinfunction "C6_11") (pintype "passive"))
    )
    (net (code "81") (name "Net-(U1A-VREFHI)") (class "Default")
      (node (ref "C24") (pin "1") (pinfunction "1_1") (pintype "passive"))
      (node (ref "J15") (pin "1") (pinfunction "1_1") (pintype "passive"))
      (node (ref "U1") (pin "20") (pinfunction "VREFHI_20") (pintype "passive"))
    )
    (net (code "82") (name "VDD") (class "Default")
      (node (ref "C10") (pin "1") (pinfunction "1_1") (pintype "passive"))
      (node (ref "C11") (pin "1") (pinfunction "1_1") (pintype "passive"))
      (node (ref "C12") (pin "1") (pinfunction "1_1") (pintype "passive"))
      (node (ref "C13") (pin "1") (pinfunction "1_1") (pintype "passive"))
      (node (ref "C9") (pin "2") (pinfunction "2_2") (pintype "passive"))
      (node (ref "U1") (pin "31") (pinfunction "VDD_31") (pintype "power_in"))
      (node (ref "U1") (pin "53") (pinfunction "VDD_53") (pintype "power_in"))
      (node (ref "U1") (pin "71") (pinfunction "VDD_71") (pintype "power_in"))
      (node (ref "U1") (pin "8") (pinfunction "VDD_8") (pintype "power_in"))
    )
    (net (code "83") (name "VDDA") (class "Default")
      (node (ref "C14") (pin "2") (pinfunction "2_2") (pintype "passive"))
      (node (ref "C15") (pin "1") (pinfunction "1_1") (pintype "passive"))
      (node (ref "L2") (pin "1") (pinfunction "1_1") (pintype "passive"))
      (node (ref "U1") (pin "26") (pinfunction "VDDA_26") (pintype "power_in"))
    )
    (net (code "84") (name "VDDIO") (class "Default")
      (node (ref "C19") (pin "1") (pinfunction "1_1") (pintype "passive"))
      (node (ref "C20") (pin "2") (pinfunction "2_2") (pintype "passive"))
      (node (ref "C21") (pin "2") (pinfunction "2_2") (pintype "passive"))
      (node (ref "C22") (pin "2") (pinfunction "2_2") (pintype "passive"))
      (node (ref "C23") (pin "2") (pinfunction "2_2") (pintype "passive"))
      (node (ref "L3") (pin "2") (pinfunction "2_2") (pintype "passive"))
      (node (ref "U1") (pin "32") (pinfunction "VDDIO_32") (pintype "power_in"))
      (node (ref "U1") (pin "52") (pinfunction "VDDIO_52") (pintype "power_in"))
      (node (ref "U1") (pin "7") (pinfunction "VDDIO_7") (pintype "power_in"))
      (node (ref "U1") (pin "72") (pinfunction "VDDIO_72") (pintype "power_in"))
    )
    (net (code "85") (name "unconnected-(U1D-FLT1-Pad34)") (class "Default")
      (node (ref "U1") (pin "34") (pinfunction "FLT1_34") (pintype "bidirectional+no_connect"))
    )
    (net (code "86") (name "unconnected-(U1D-FLT2-Pad33)") (class "Default")
      (node (ref "U1") (pin "33") (pinfunction "FLT2_33") (pintype "bidirectional+no_connect"))
    )
  )
)
